# extern.net
KiCad netlist of a schematic drawn in Altium Designer
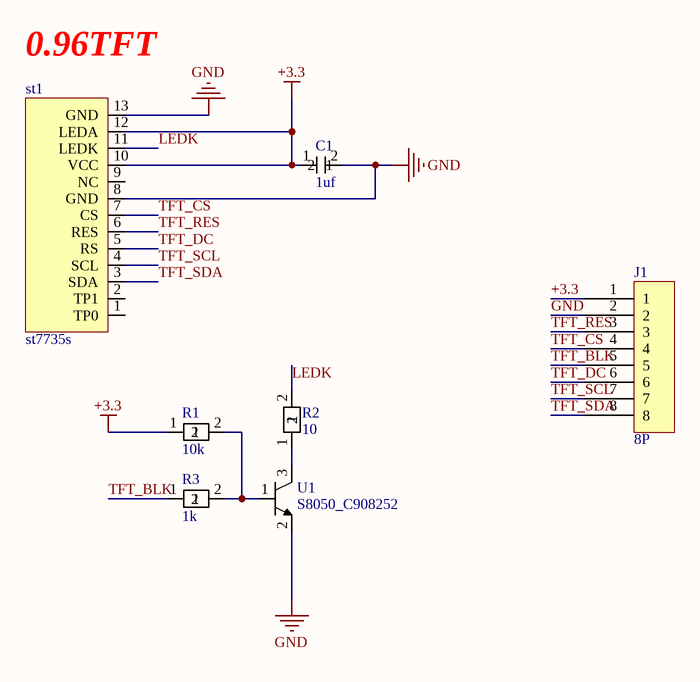
[diagram p0: extern.SchDoc]

(export (version "E")
  (design (tool "Eeschema 10.0.6"))
  (components
    (comp (ref "C1") (value "1uf") (footprint "C0805") (libsource (lib "My") (part "C0805")))
    (comp (ref "J1") (value "8P") (footprint "8P-P2.54") (libsource (lib "My") (part "8P")))
    (comp (ref "R1") (value "10k") (footprint "R0805") (libsource (lib "Schlib1") (part "R0805")))
    (comp (ref "R2") (value "10") (footprint "R0805") (libsource (lib "Schlib1") (part "R0805")))
    (comp (ref "R3") (value "1k") (footprint "R0805") (libsource (lib "Schlib1") (part "R0805")))
    (comp (ref "st1") (value "st7735s") (footprint "st7735s") (libsource (lib "Schlib1") (part "st7735s")))
    (comp (ref "U1") (value "S8050_C908252") (footprint "s8050") (libsource (lib "My") (part "s8050")))
  )
  (nets
    (net (code "1") (name "+3.3") (class "Default")
      (node (ref "C1") (pin "1") (pinfunction "1_1") (pintype "passive"))
      (node (ref "J1") (pin "1") (pinfunction "1_1") (pintype "passive"))
      (node (ref "R1") (pin "1") (pinfunction "1_1") (pintype "passive"))
      (node (ref "st1") (pin "10") (pinfunction "VCC_10") (pintype "passive"))
      (node (ref "st1") (pin "12") (pinfunction "LEDA_12") (pintype "passive"))
    )
    (net (code "2") (name "/LEDK") (class "Default")
      (node (ref "R2") (pin "2") (pinfunction "2_2") (pintype "passive"))
      (node (ref "st1") (pin "11") (pinfunction "LEDK_11") (pintype "passive"))
    )
    (net (code "3") (name "/TFT_BLK") (class "Default")
      (node (ref "J1") (pin "5") (pinfunction "5_5") (pintype "passive"))
      (node (ref "R3") (pin "1") (pinfunction "1_1") (pintype "passive"))
    )
    (net (code "4") (name "/TFT_CS") (class "Default")
      (node (ref "J1") (pin "4") (pinfunction "4_4") (pintype "passive"))
      (node (ref "st1") (pin "7") (pinfunction "CS_7") (pintype "passive"))
    )
    (net (code "5") (name "/TFT_DC") (class "Default")
      (node (ref "J1") (pin "6") (pinfunction "6_6") (pintype "passive"))
      (node (ref "st1") (pin "5") (pinfunction "RS_5") (pintype "passive"))
    )
    (net (code "6") (name "/TFT_RES") (class "Default")
      (node (ref "J1") (pin "3") (pinfunction "3_3") (pintype "passive"))
      (node (ref "st1") (pin "6") (pinfunction "RES_6") (pintype "passive"))
    )
    (net (code "7") (name "/TFT_SCL") (class "Default")
      (node (ref "J1") (pin "7") (pinfunction "7_7") (pintype "passive"))
      (node (ref "st1") (pin "4") (pinfunction "SCL_4") (pintype "passive"))
    )
    (net (code "8") (name "/TFT_SDA") (class "Default")
      (node (ref "J1") (pin "8") (pinfunction "8_8") (pintype "passive"))
      (node (ref "st1") (pin "3") (pinfunction "SDA_3") (pintype "passive"))
    )
    (net (code "9") (name "GND") (class "Default")
      (node (ref "C1") (pin "2") (pinfunction "2_2") (pintype "passive"))
      (node (ref "J1") (pin "2") (pinfunction "2_2") (pintype "passive"))
      (node (ref "U1") (pin "2") (pinfunction "E_2") (pintype "passive"))
      (node (ref "st1") (pin "13") (pinfunction "GND_13") (pintype "passive"))
      (node (ref "st1") (pin "8") (pinfunction "GND_8") (pintype "passive"))
    )
    (net (code "10") (name "Net-(U1-B)") (class "Default")
      (node (ref "R1") (pin "2") (pinfunction "2_2") (pintype "passive"))
      (node (ref "R3") (pin "2") (pinfunction "2_2") (pintype "passive"))
      (node (ref "U1") (pin "1") (pinfunction "B_1") (pintype "passive"))
    )
    (net (code "11") (name "Net-(U1-C)") (class "Default")
      (node (ref "R2") (pin "1") (pinfunction "1_1") (pintype "passive"))
      (node (ref "U1") (pin "3") (pinfunction "C_3") (pintype "passive"))
    )
    (net (code "12") (name "unconnected-(st1-NC-Pad9)") (class "Default")
      (node (ref "st1") (pin "9") (pinfunction "NC_9") (pintype "passive"))
    )
    (net (code "13") (name "unconnected-(st1-TP0-Pad1)") (class "Default")
      (node (ref "st1") (pin "1") (pinfunction "TP0_1") (pintype "passive"))
    )
    (net (code "14") (name "unconnected-(st1-TP1-Pad2)") (class "Default")
      (node (ref "st1") (pin "2") (pinfunction "TP1_2") (pintype "passive"))
    )
  )
)
